# SCH_Lora_Messenger_2024-02-14.net
KiCad netlist of a schematic drawn in EasyEDA
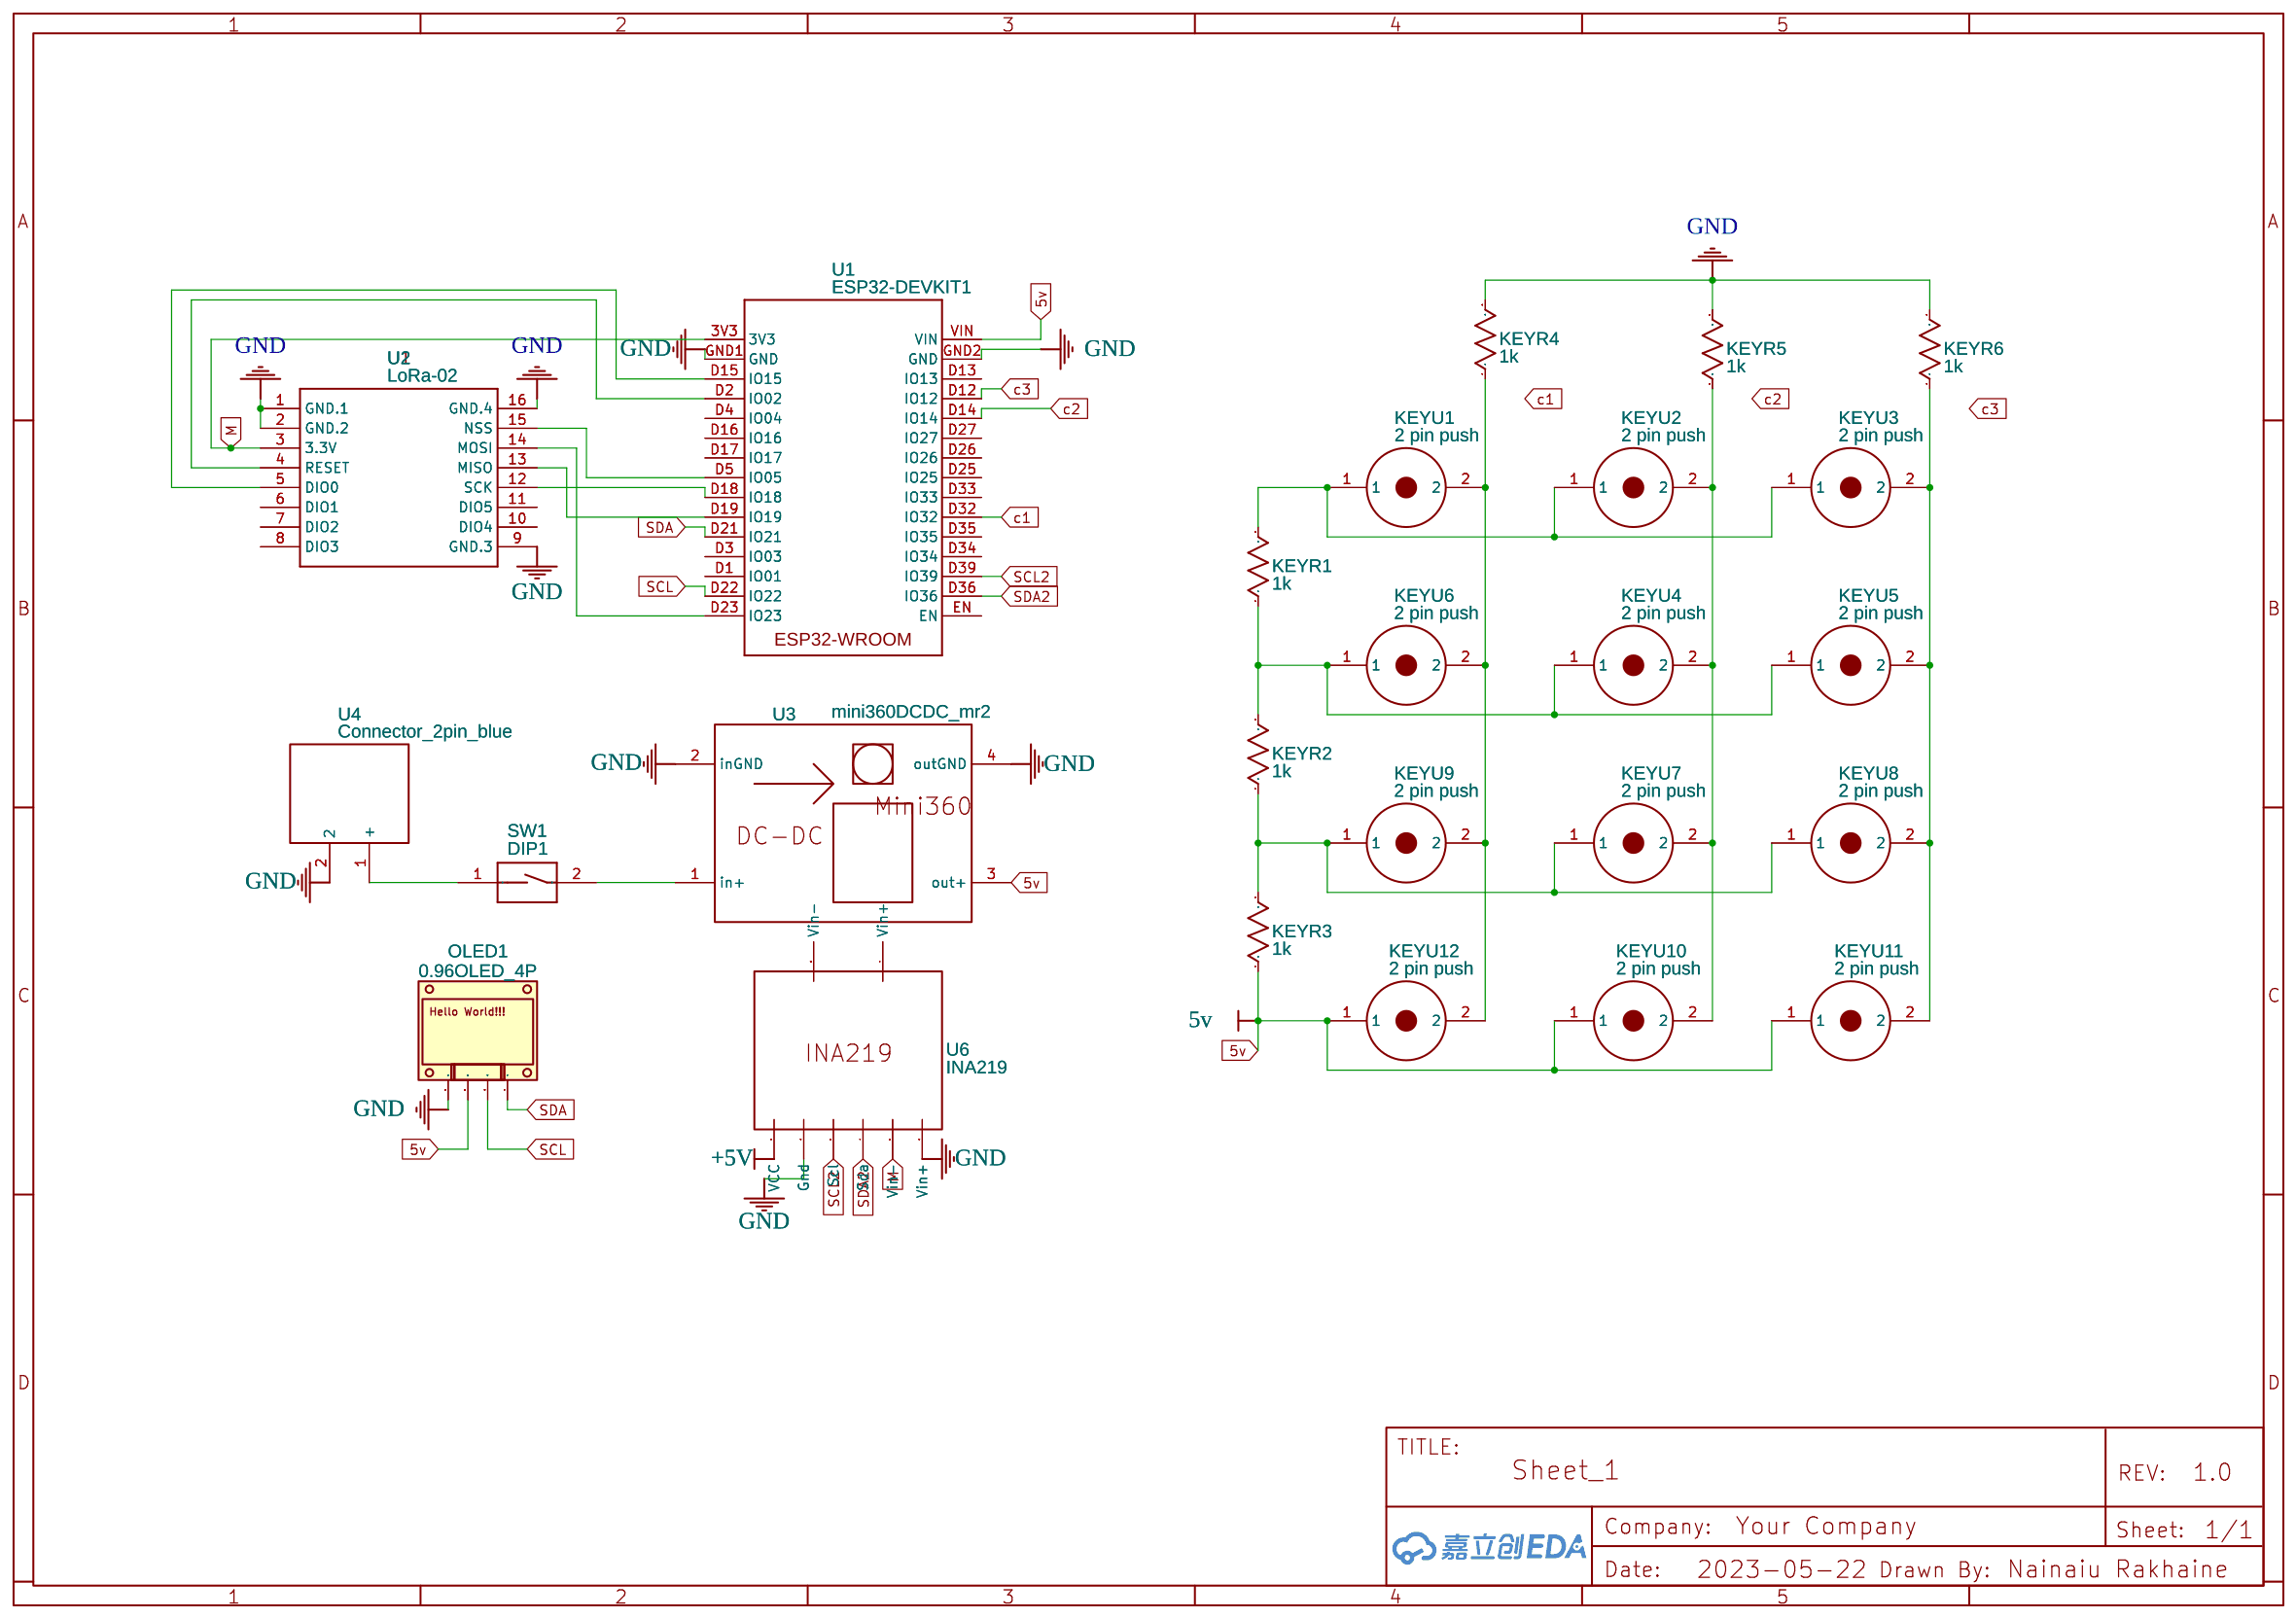
[diagram p0: schematic sheet]

(export (version "E")
  (design (tool "Eeschema 10.0.6"))
  (components
    (comp (ref "KEYR1") (value "1k") (libsource (lib "") (part "R_AXIAL-0.4_US")))
    (comp (ref "KEYR2") (value "1k") (libsource (lib "") (part "R_AXIAL-0.4_US")))
    (comp (ref "KEYR3") (value "1k") (libsource (lib "") (part "R_AXIAL-0.4_US")))
    (comp (ref "KEYR4") (value "1k") (libsource (lib "") (part "R_AXIAL-0.4_US")))
    (comp (ref "KEYR5") (value "1k") (libsource (lib "") (part "R_AXIAL-0.4_US")))
    (comp (ref "KEYR6") (value "1k") (libsource (lib "") (part "R_AXIAL-0.4_US")))
    (comp (ref "KEYU1") (value "2 pin push") (libsource (lib "") (part "2 pin push")))
    (comp (ref "KEYU2") (value "2 pin push") (libsource (lib "") (part "2 pin push")))
    (comp (ref "KEYU3") (value "2 pin push") (libsource (lib "") (part "2 pin push")))
    (comp (ref "KEYU4") (value "2 pin push") (libsource (lib "") (part "2 pin push")))
    (comp (ref "KEYU5") (value "2 pin push") (libsource (lib "") (part "2 pin push")))
    (comp (ref "KEYU6") (value "2 pin push") (libsource (lib "") (part "2 pin push")))
    (comp (ref "KEYU7") (value "2 pin push") (libsource (lib "") (part "2 pin push")))
    (comp (ref "KEYU8") (value "2 pin push") (libsource (lib "") (part "2 pin push")))
    (comp (ref "KEYU9") (value "2 pin push") (libsource (lib "") (part "2 pin push")))
    (comp (ref "KEYU10") (value "2 pin push") (libsource (lib "") (part "2 pin push")))
    (comp (ref "KEYU11") (value "2 pin push") (libsource (lib "") (part "2 pin push")))
    (comp (ref "KEYU12") (value "2 pin push") (libsource (lib "") (part "2 pin push")))
    (comp (ref "OLED1") (value "0.96OLED_4P") (libsource (lib "") (part "0.96OLED_4P")))
    (comp (ref "SW1")
      (value "DIP1")
      (fields
        (field (name "Manufacturer Part") "A6TN-1101")
        (field (name "Manufacturer") "Omron Electronics Inc-EMC Div")
      )
      (libsource (lib "") (part "DIP1"))
    )
    (comp (ref "U1") (value "ESP32-DEVKIT1") (libsource (lib "") (part "ESP32-DEVKIT1")))
    (comp (ref "U2") (value "LoRa-02") (libsource (lib "") (part "LoRa-02")))
    (comp (ref "U3") (value "mini360DCDC_mr2") (libsource (lib "") (part "mini360DCDC_mr2")))
    (comp (ref "U4") (value "Connector_2pin_blue") (libsource (lib "") (part "Connector_2pin_blue")))
    (comp (ref "U6") (value "INA219") (libsource (lib "") (part "INA219")))
  )
  (nets
    (net (code "2") (name "5v") (class "Default")
      (node (ref "KEYR3") (pin "1") (pinfunction "1_1") (pintype "unspecified"))
      (node (ref "KEYU10") (pin "1") (pinfunction "1_1") (pintype "unspecified"))
      (node (ref "KEYU11") (pin "1") (pinfunction "1_1") (pintype "unspecified"))
      (node (ref "KEYU12") (pin "1") (pinfunction "1_1") (pintype "unspecified"))
      (node (ref "OLED1") (pin "2") (pinfunction "2_2") (pintype "unspecified"))
      (node (ref "U1") (pin "VIN") (pinfunction "VIN_VIN") (pintype "bidirectional"))
      (node (ref "U3") (pin "3") (pinfunction "out+_3") (pintype "unspecified"))
    )
    (net (code "3") (name "GND") (class "Default")
      (node (ref "KEYR4") (pin "2") (pinfunction "2_2") (pintype "unspecified"))
      (node (ref "KEYR5") (pin "2") (pinfunction "2_2") (pintype "unspecified"))
      (node (ref "KEYR6") (pin "2") (pinfunction "2_2") (pintype "unspecified"))
      (node (ref "OLED1") (pin "1") (pinfunction "1_1") (pintype "unspecified"))
      (node (ref "U1") (pin "GND1") (pinfunction "GND_GND1") (pintype "bidirectional"))
      (node (ref "U1") (pin "GND2") (pinfunction "GND_GND2") (pintype "bidirectional"))
      (node (ref "U2") (pin "1") (pinfunction "GND.1_1") (pintype "passive"))
      (node (ref "U2") (pin "16") (pinfunction "GND.4_16") (pintype "passive"))
      (node (ref "U2") (pin "2") (pinfunction "GND.2_2") (pintype "passive"))
      (node (ref "U2") (pin "9") (pinfunction "GND.3_9") (pintype "passive"))
      (node (ref "U3") (pin "2") (pinfunction "inGND_2") (pintype "unspecified"))
      (node (ref "U3") (pin "4") (pinfunction "outGND_4") (pintype "unspecified"))
      (node (ref "U4") (pin "2") (pinfunction "2_2") (pintype "unspecified"))
    )
    (net (code "4") (name "M") (class "Default")
      (node (ref "U1") (pin "3V3") (pinfunction "3V3_3V3") (pintype "bidirectional"))
      (node (ref "U2") (pin "3") (pinfunction "3.3V_3") (pintype "passive"))
    )
    (net (code "5") (name "Net-(KEYR1-Pad1)") (class "Default")
      (node (ref "KEYR1") (pin "1") (pinfunction "1_1") (pintype "unspecified"))
      (node (ref "KEYR2") (pin "2") (pinfunction "2_2") (pintype "unspecified"))
      (node (ref "KEYU4") (pin "1") (pinfunction "1_1") (pintype "unspecified"))
      (node (ref "KEYU5") (pin "1") (pinfunction "1_1") (pintype "unspecified"))
      (node (ref "KEYU6") (pin "1") (pinfunction "1_1") (pintype "unspecified"))
    )
    (net (code "6") (name "Net-(KEYR1-Pad2)") (class "Default")
      (node (ref "KEYR1") (pin "2") (pinfunction "2_2") (pintype "unspecified"))
      (node (ref "KEYU1") (pin "1") (pinfunction "1_1") (pintype "unspecified"))
      (node (ref "KEYU2") (pin "1") (pinfunction "1_1") (pintype "unspecified"))
      (node (ref "KEYU3") (pin "1") (pinfunction "1_1") (pintype "unspecified"))
    )
    (net (code "7") (name "Net-(KEYR2-Pad1)") (class "Default")
      (node (ref "KEYR2") (pin "1") (pinfunction "1_1") (pintype "unspecified"))
      (node (ref "KEYR3") (pin "2") (pinfunction "2_2") (pintype "unspecified"))
      (node (ref "KEYU7") (pin "1") (pinfunction "1_1") (pintype "unspecified"))
      (node (ref "KEYU8") (pin "1") (pinfunction "1_1") (pintype "unspecified"))
      (node (ref "KEYU9") (pin "1") (pinfunction "1_1") (pintype "unspecified"))
    )
    (net (code "8") (name "Net-(KEYR4-Pad1)") (class "Default")
      (node (ref "KEYR4") (pin "1") (pinfunction "1_1") (pintype "unspecified"))
      (node (ref "KEYU1") (pin "2") (pinfunction "2_2") (pintype "unspecified"))
      (node (ref "KEYU12") (pin "2") (pinfunction "2_2") (pintype "unspecified"))
      (node (ref "KEYU6") (pin "2") (pinfunction "2_2") (pintype "unspecified"))
      (node (ref "KEYU9") (pin "2") (pinfunction "2_2") (pintype "unspecified"))
    )
    (net (code "9") (name "Net-(KEYR5-Pad1)") (class "Default")
      (node (ref "KEYR5") (pin "1") (pinfunction "1_1") (pintype "unspecified"))
      (node (ref "KEYU10") (pin "2") (pinfunction "2_2") (pintype "unspecified"))
      (node (ref "KEYU2") (pin "2") (pinfunction "2_2") (pintype "unspecified"))
      (node (ref "KEYU4") (pin "2") (pinfunction "2_2") (pintype "unspecified"))
      (node (ref "KEYU7") (pin "2") (pinfunction "2_2") (pintype "unspecified"))
    )
    (net (code "10") (name "Net-(KEYR6-Pad1)") (class "Default")
      (node (ref "KEYR6") (pin "1") (pinfunction "1_1") (pintype "unspecified"))
      (node (ref "KEYU11") (pin "2") (pinfunction "2_2") (pintype "unspecified"))
      (node (ref "KEYU3") (pin "2") (pinfunction "2_2") (pintype "unspecified"))
      (node (ref "KEYU5") (pin "2") (pinfunction "2_2") (pintype "unspecified"))
      (node (ref "KEYU8") (pin "2") (pinfunction "2_2") (pintype "unspecified"))
    )
    (net (code "11") (name "Net-(U1-IO02)") (class "Default")
      (node (ref "U1") (pin "D2") (pinfunction "IO02_D2") (pintype "bidirectional"))
      (node (ref "U2") (pin "4") (pinfunction "RESET_4") (pintype "unspecified"))
    )
    (net (code "12") (name "Net-(U1-IO05)") (class "Default")
      (node (ref "U1") (pin "D5") (pinfunction "IO05_D5") (pintype "bidirectional"))
      (node (ref "U2") (pin "15") (pinfunction "NSS_15") (pintype "unspecified"))
    )
    (net (code "13") (name "Net-(U1-IO15)") (class "Default")
      (node (ref "U1") (pin "D15") (pinfunction "IO15_D15") (pintype "bidirectional"))
      (node (ref "U2") (pin "5") (pinfunction "DIO0_5") (pintype "unspecified"))
    )
    (net (code "14") (name "Net-(U1-IO18)") (class "Default")
      (node (ref "U1") (pin "D18") (pinfunction "IO18_D18") (pintype "bidirectional"))
      (node (ref "U2") (pin "12") (pinfunction "SCK_12") (pintype "unspecified"))
    )
    (net (code "15") (name "Net-(U1-IO19)") (class "Default")
      (node (ref "U1") (pin "D19") (pinfunction "IO19_D19") (pintype "bidirectional"))
      (node (ref "U2") (pin "13") (pinfunction "MISO_13") (pintype "unspecified"))
    )
    (net (code "16") (name "Net-(U1-IO23)") (class "Default")
      (node (ref "U1") (pin "D23") (pinfunction "IO23_D23") (pintype "bidirectional"))
      (node (ref "U2") (pin "14") (pinfunction "MOSI_14") (pintype "unspecified"))
    )
    (net (code "17") (name "Net-(U3-in+)") (class "Default")
      (node (ref "SW1") (pin "2") (pinfunction "2_2") (pintype "unspecified"))
      (node (ref "U3") (pin "1") (pinfunction "in+_1") (pintype "unspecified"))
    )
    (net (code "18") (name "Net-(U4-+)") (class "Default")
      (node (ref "SW1") (pin "1") (pinfunction "1_1") (pintype "unspecified"))
      (node (ref "U4") (pin "1") (pinfunction "+_1") (pintype "unspecified"))
    )
    (net (code "19") (name "SCL") (class "Default")
      (node (ref "OLED1") (pin "3") (pinfunction "3_3") (pintype "unspecified"))
      (node (ref "U1") (pin "D22") (pinfunction "IO22_D22") (pintype "bidirectional"))
    )
    (net (code "20") (name "SCL2") (class "Default")
      (node (ref "U1") (pin "D39") (pinfunction "IO39_D39") (pintype "bidirectional"))
    )
    (net (code "21") (name "SDA") (class "Default")
      (node (ref "OLED1") (pin "4") (pinfunction "4_4") (pintype "unspecified"))
      (node (ref "U1") (pin "D21") (pinfunction "IO21_D21") (pintype "bidirectional"))
    )
    (net (code "22") (name "SDA2") (class "Default")
      (node (ref "U1") (pin "D36") (pinfunction "IO36_D36") (pintype "bidirectional"))
    )
    (net (code "23") (name "c1") (class "Default")
      (node (ref "U1") (pin "D32") (pinfunction "IO32_D32") (pintype "bidirectional"))
    )
    (net (code "24") (name "c2") (class "Default")
      (node (ref "U1") (pin "D14") (pinfunction "IO14_D14") (pintype "bidirectional"))
    )
    (net (code "25") (name "c3") (class "Default")
      (node (ref "U1") (pin "D12") (pinfunction "IO12_D12") (pintype "bidirectional"))
    )
    (net (code "26") (name "unconnected-(U1-IO01-PadD1)") (class "Default")
      (node (ref "U1") (pin "D1") (pinfunction "IO01_D1") (pintype "bidirectional"))
    )
    (net (code "27") (name "unconnected-(U1-IO03-PadD3)") (class "Default")
      (node (ref "U1") (pin "D3") (pinfunction "IO03_D3") (pintype "bidirectional"))
    )
    (net (code "28") (name "unconnected-(U1-IO04-PadD4)") (class "Default")
      (node (ref "U1") (pin "D4") (pinfunction "IO04_D4") (pintype "bidirectional"))
    )
    (net (code "29") (name "unconnected-(U1-IO13-PadD13)") (class "Default")
      (node (ref "U1") (pin "D13") (pinfunction "IO13_D13") (pintype "bidirectional"))
    )
    (net (code "30") (name "unconnected-(U1-IO16-PadD16)") (class "Default")
      (node (ref "U1") (pin "D16") (pinfunction "IO16_D16") (pintype "bidirectional"))
    )
    (net (code "31") (name "unconnected-(U1-IO17-PadD17)") (class "Default")
      (node (ref "U1") (pin "D17") (pinfunction "IO17_D17") (pintype "bidirectional"))
    )
    (net (code "32") (name "unconnected-(U1-IO25-PadD25)") (class "Default")
      (node (ref "U1") (pin "D25") (pinfunction "IO25_D25") (pintype "bidirectional"))
    )
    (net (code "33") (name "unconnected-(U1-IO26-PadD26)") (class "Default")
      (node (ref "U1") (pin "D26") (pinfunction "IO26_D26") (pintype "bidirectional"))
    )
    (net (code "34") (name "unconnected-(U1-IO27-PadD27)") (class "Default")
      (node (ref "U1") (pin "D27") (pinfunction "IO27_D27") (pintype "bidirectional"))
    )
    (net (code "35") (name "unconnected-(U1-IO33-PadD33)") (class "Default")
      (node (ref "U1") (pin "D33") (pinfunction "IO33_D33") (pintype "bidirectional"))
    )
    (net (code "36") (name "unconnected-(U1-IO34-PadD34)") (class "Default")
      (node (ref "U1") (pin "D34") (pinfunction "IO34_D34") (pintype "bidirectional"))
    )
    (net (code "37") (name "unconnected-(U1-IO35-PadD35)") (class "Default")
      (node (ref "U1") (pin "D35") (pinfunction "IO35_D35") (pintype "bidirectional"))
    )
    (net (code "38") (name "unconnected-(U1-PadEN)") (class "Default")
      (node (ref "U1") (pin "EN") (pinfunction "EN_EN") (pintype "bidirectional"))
    )
    (net (code "39") (name "unconnected-(U2-DIO1-Pad6)") (class "Default")
      (node (ref "U2") (pin "6") (pinfunction "DIO1_6") (pintype "unspecified"))
    )
    (net (code "40") (name "unconnected-(U2-DIO2-Pad7)") (class "Default")
      (node (ref "U2") (pin "7") (pinfunction "DIO2_7") (pintype "unspecified"))
    )
    (net (code "41") (name "unconnected-(U2-DIO3-Pad8)") (class "Default")
      (node (ref "U2") (pin "8") (pinfunction "DIO3_8") (pintype "unspecified"))
    )
    (net (code "42") (name "unconnected-(U2-DIO4-Pad10)") (class "Default")
      (node (ref "U2") (pin "10") (pinfunction "DIO4_10") (pintype "unspecified"))
    )
    (net (code "43") (name "unconnected-(U2-DIO5-Pad11)") (class "Default")
      (node (ref "U2") (pin "11") (pinfunction "DIO5_11") (pintype "unspecified"))
    )
    (net (code "44") (name "unconnected-(U6-Gnd-Pad2)") (class "Default")
      (node (ref "U6") (pin "2") (pinfunction "Gnd_2") (pintype "unspecified"))
    )
    (net (code "45") (name "unconnected-(U6-Scl-Pad3)") (class "Default")
      (node (ref "U6") (pin "3") (pinfunction "Scl_3") (pintype "unspecified"))
    )
    (net (code "46") (name "unconnected-(U6-Sda-Pad4)") (class "Default")
      (node (ref "U6") (pin "4") (pinfunction "Sda_4") (pintype "unspecified"))
    )
    (net (code "47") (name "unconnected-(U6-VCC-Pad1)") (class "Default")
      (node (ref "U6") (pin "1") (pinfunction "VCC_1") (pintype "unspecified"))
    )
    (net (code "48") (name "unconnected-(U6-Vin+-Pad6)") (class "Default")
      (node (ref "U6") (pin "6") (pinfunction "Vin+_6") (pintype "unspecified"))
    )
    (net (code "49") (name "unconnected-(U6-Vin+-Pad7)") (class "Default")
      (node (ref "U6") (pin "7") (pinfunction "Vin+_7") (pintype "unspecified"))
    )
    (net (code "50") (name "unconnected-(U6-Vin--Pad5)") (class "Default")
      (node (ref "U6") (pin "5") (pinfunction "Vin-_5") (pintype "unspecified"))
    )
    (net (code "51") (name "unconnected-(U6-Vin--Pad8)") (class "Default")
      (node (ref "U6") (pin "8") (pinfunction "Vin-_8") (pintype "unspecified"))
    )
  )
)
